# POWER_DISTRIBUTION.net
KiCad netlist of a schematic drawn in Altium Designer
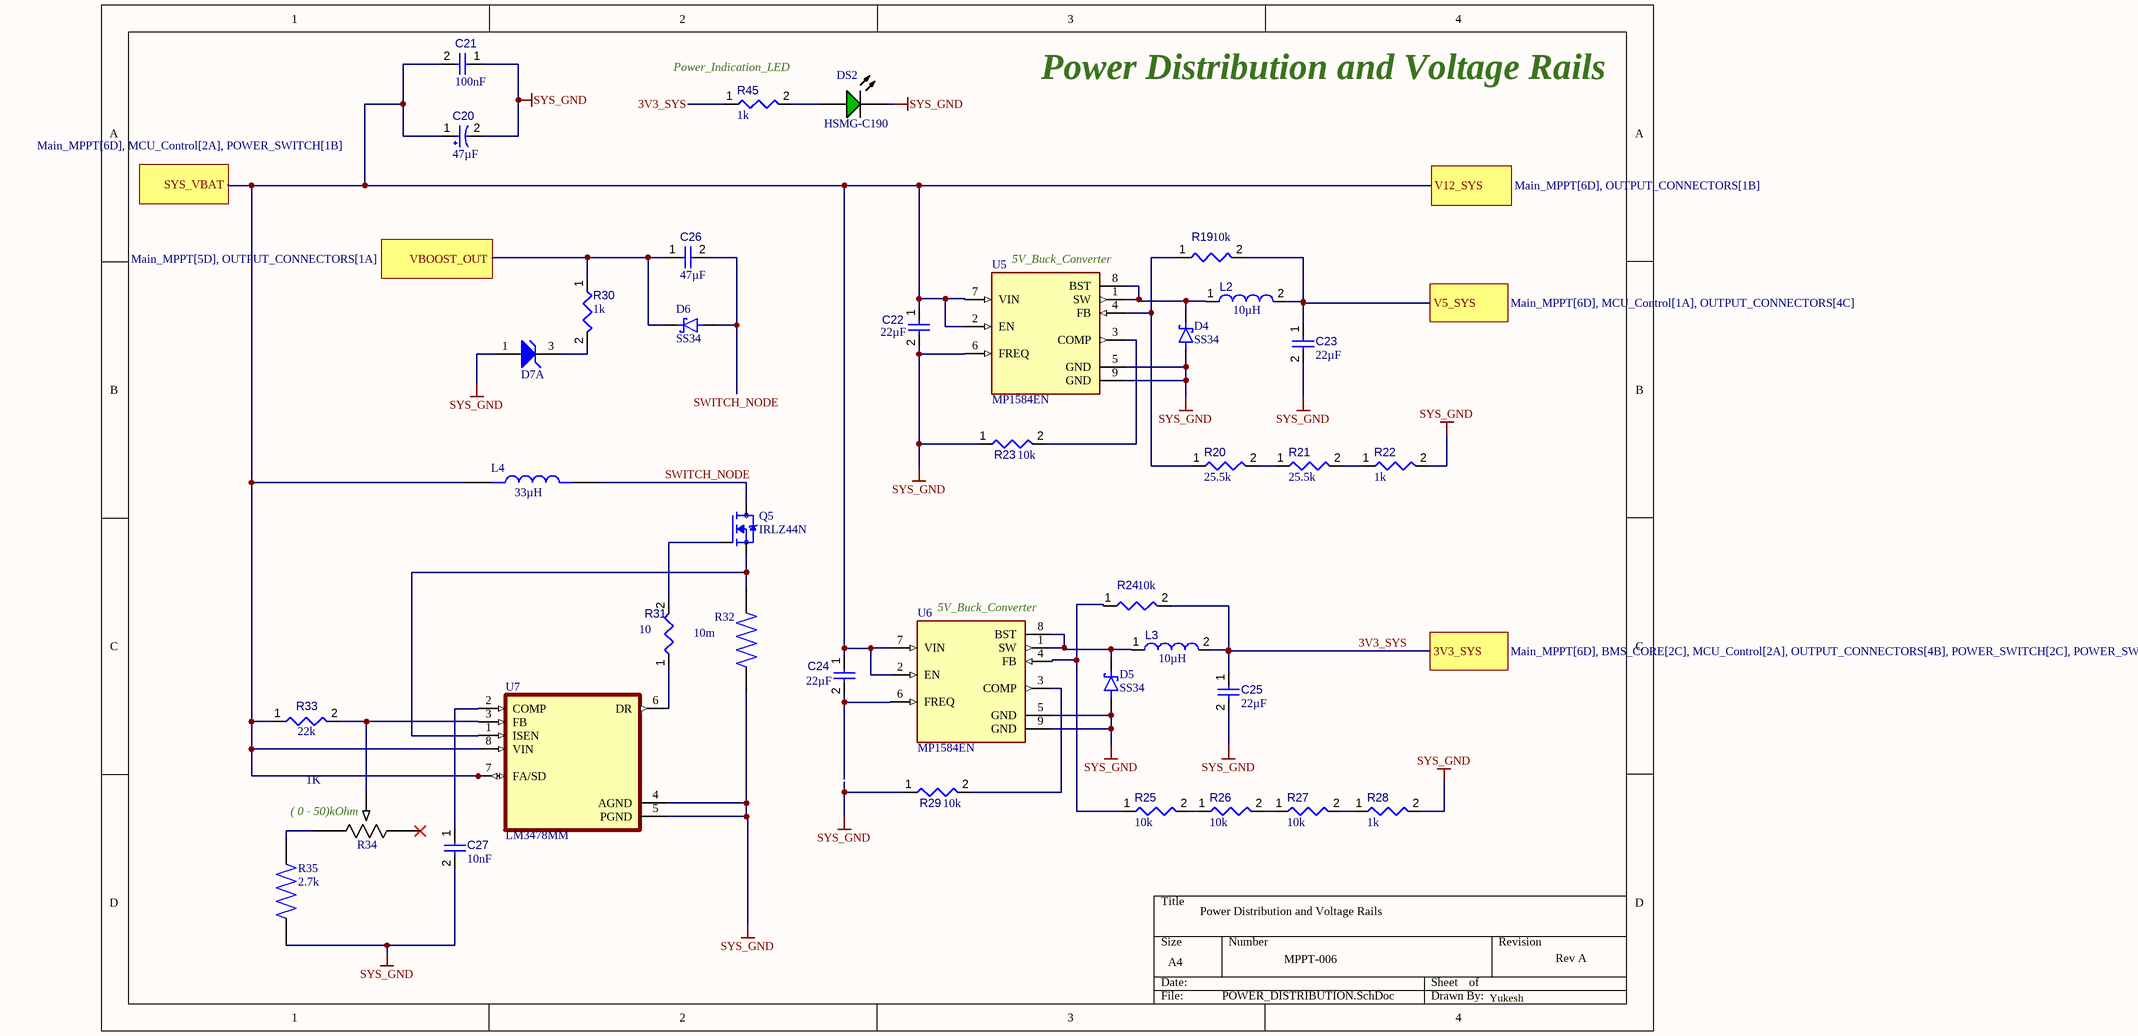
[diagram p0: POWER_DISTRIBUTION.SchDoc]

(export (version "E")
  (design (tool "Eeschema 10.0.6"))
  (components
    (comp (ref "C20")
      (value "47µF")
      (footprint "CAPPR55-250-1120X630X1220")
      (description "Aluminum Electrolytic Capacitor, 47 uF, +/- 20%, 50 V, -40 to 85 degC, 2-Pin THD, RoHS, Bulk")
      (fields (field (name "MANUFACTURER") "Panasonic") (field (name "TOLERANCE") "20%"))
      (libsource (lib "YUKESH S") (part "CAP-P-2"))
    )
    (comp (ref "C21")
      (value "100nF")
      (footprint "CAPC0402(1005)60_L")
      (description "Chip Capacitor, 100nF +/-20%, 50V, 0402, Thickness 0.6 mm")
      (fields (field (name "TOLERANCE") "10%") (field (name "Comment") "Capacitor 100nF +/-20% 50V 0402"))
      (libsource (lib "YUKESH S") (part "CAP-NP-2"))
    )
    (comp (ref "C22")
      (value "22µF")
      (footprint "CAPC0805(2012)145_L")
      (description "Chip Capacitor, 22µF +/-40%, 16V, 0805, Thickness 1.45 mm")
      (fields (field (name "TOLERANCE") "5%") (field (name "Comment") "Capacitor 22µF +/-40% 16V 0805"))
      (libsource (lib "YUKESH S") (part "CAP-NP-2"))
    )
    (comp (ref "C23")
      (value "22µF")
      (footprint "CAPC0805(2012)145_L")
      (description "Chip Capacitor, 22µF +/-40%, 16V, 0805, Thickness 1.45 mm")
      (fields (field (name "TOLERANCE") "5%") (field (name "Comment") "Capacitor 22µF +/-40% 16V 0805"))
      (libsource (lib "YUKESH S") (part "CAP-NP-2"))
    )
    (comp (ref "C24")
      (value "22µF")
      (footprint "CAPC0805(2012)145_L")
      (description "Chip Capacitor, 22µF +/-40%, 16V, 0805, Thickness 1.45 mm")
      (fields (field (name "TOLERANCE") "5%") (field (name "Comment") "Capacitor 22µF +/-40% 16V 0805"))
      (libsource (lib "YUKESH S") (part "CAP-NP-2"))
    )
    (comp (ref "C25")
      (value "22µF")
      (footprint "CAPC0805(2012)145_L")
      (description "Chip Capacitor, 22µF +/-40%, 16V, 0805, Thickness 1.45 mm")
      (fields (field (name "TOLERANCE") "5%") (field (name "Comment") "Capacitor 22µF +/-40% 16V 0805"))
      (libsource (lib "YUKESH S") (part "CAP-NP-2"))
    )
    (comp (ref "C26")
      (value "47µF")
      (footprint "CAPC0805(2012)145_L")
      (description "Chip Capacitor, 47µF +/-40%, 6.3V, 0805, Thickness 1.45 mm")
      (fields (field (name "TOLERANCE") "10%") (field (name "Comment") "Capacitor 47µF +/-40% 6.3V 0805"))
      (libsource (lib "YUKESH S") (part "CAP-NP-2"))
    )
    (comp (ref "C27")
      (value "10nF")
      (footprint "CAPC0402(1005)60_L")
      (description "Chip Capacitor, 10nF +/-20%, 50V, 0402, Thickness 0.6 mm")
      (fields (field (name "TOLERANCE") "5%") (field (name "Comment") "Capacitor 10nF +/-20% 50V 0402"))
      (libsource (lib "YUKESH S") (part "CAP-NP-2"))
    )
    (comp (ref "D4")
      (value "SS34")
      (footprint "Copy of DIOM7959X265N")
      (description "Diode Schottky 40 V 3A Surface Mount SMC (DO-214AB)")
      (fields (field (name "MF") "onsemi"))
      (libsource (lib "YUKESH S") (part "SS34"))
    )
    (comp (ref "D5")
      (value "SS34")
      (footprint "Copy of DIOM7959X265N")
      (description "Diode Schottky 40 V 3A Surface Mount SMC (DO-214AB)")
      (fields (field (name "MF") "onsemi"))
      (libsource (lib "YUKESH S") (part "SS34"))
    )
    (comp (ref "D6")
      (value "SS34")
      (footprint "Copy of DIOM7959X265N")
      (description "Diode Schottky 40 V 3A Surface Mount SMC (DO-214AB)")
      (fields (field (name "MF") "onsemi"))
      (libsource (lib "YUKESH S") (part "SS34"))
    )
    (comp (ref "D7")
      (value "BZX84C47LT1G")
      (footprint "ONSC-SOT-23-3-318-08_V")
      (description "Zener Voltage Regulator, 225 mW, 3-Pin SOT-23, Pb-Free, Tape and Reel")
      (fields (field (name "MANUFACTURER") "On Semiconductor"))
      (libsource (lib "Altium Content Vault") (part "ONSC-A1K3-3"))
    )
    (comp (ref "DS2")
      (value "HSMG-C190")
      (footprint "AVAG-HSMX-C190_V")
      (description "LED Uni-Color Green, 52 mW, 20 mA, -40 to 85 degC, 2-Pin SMD, RoHS, Tape and Reel")
      (fields (field (name "POWER") "52mW") (field (name "MANUFACTURER") "Avago"))
      (libsource (lib "YUKESH S") (part "LED-GREEN-AK-2"))
    )
    (comp (ref "L2")
      (value "10µH")
      (footprint "INDR62-500-1100X850X1100")
      (description "Radial Inductor, 10 uH, +/- 10%, 3 A, -55 to 105 degC, 2-Pin THD, RoHS, Bulk")
      (fields (field (name "TOLERANCE") "10%") (field (name "MANUFACTURER") "Bourns"))
      (libsource (lib "YUKESH S") (part "IND-2"))
    )
    (comp (ref "L3")
      (value "10µH")
      (footprint "INDR62-500-1100X850X1100")
      (description "Radial Inductor, 10 uH, +/- 10%, 3 A, -55 to 105 degC, 2-Pin THD, RoHS, Bulk")
      (fields (field (name "TOLERANCE") "10%") (field (name "MANUFACTURER") "Bourns"))
      (libsource (lib "YUKESH S") (part "IND-2"))
    )
    (comp (ref "L4")
      (value "33µH")
      (footprint "IND_ETQP4M330YFN")
      (description "FIXED IND 33UH 2.5A 189.2MOHM SM")
      (fields (field (name "MF") "Panasonic") (field (name "MP") "ETQP4M330YFN"))
      (libsource (lib "YUKESH S") (part "ETQP4M330YFN"))
    )
    (comp (ref "Q5")
      (value "IRLZ44N")
      (footprint "TO254P1054X469X1930-3")
      (description "N-Channel 55 V 47A (Tc) 3.8W (Ta), 110W (Tc) Surface Mount D2PAK")
      (fields (field (name "MF") "Infineon / IR"))
      (libsource (lib "YUKESH S") (part "IRLZ44N"))
    )
    (comp (ref "R19")
      (value "10k")
      (footprint "RESC0402(1005)_L")
      (description "Chip Resistor, 10 kOhms, +/-1 %, 63 mW, -55 to 125 degC, 0402")
      (fields (field (name "POWER") "63mW") (field (name "TOLERANCE") "1%"))
      (libsource (lib "YUKESH S") (part "RES-2"))
    )
    (comp (ref "R20")
      (value "25.5k")
      (footprint "RESC0402(1005)_L")
      (description "25K5 0.063W 1% 0402 (1005 Metric)  SMD")
      (fields (field (name "TOLERANCE") "1%") (field (name "POWER") "63mW"))
      (libsource (lib "YUKESH S") (part "25D5KR2F"))
    )
    (comp (ref "R21")
      (value "25.5k")
      (footprint "RESC0402(1005)_L")
      (description "25K5 0.063W 1% 0402 (1005 Metric)  SMD")
      (fields (field (name "TOLERANCE") "1%") (field (name "POWER") "63mW"))
      (libsource (lib "YUKESH S") (part "25D5KR2F"))
    )
    (comp (ref "R22")
      (value "1k")
      (footprint "RESC0402(1005)_L")
      (description "1K 0.063W 5% 0402 (1005 Metric)  SMD")
      (fields (field (name "POWER") "63mW") (field (name "TOLERANCE") "5%"))
      (libsource (lib "YUKESH S") (part "1KR2J"))
    )
    (comp (ref "R23")
      (value "10k")
      (footprint "RESC0402(1005)_L")
      (description "Chip Resistor, 10 kOhms, +/-1 %, 63 mW, -55 to 125 degC, 0402")
      (fields (field (name "POWER") "63mW") (field (name "TOLERANCE") "1%"))
      (libsource (lib "YUKESH S") (part "RES-2"))
    )
    (comp (ref "R24")
      (value "10k")
      (footprint "RESC0402(1005)_L")
      (description "Chip Resistor, 10 kOhms, +/-1 %, 63 mW, -55 to 125 degC, 0402")
      (fields (field (name "POWER") "63mW") (field (name "TOLERANCE") "1%"))
      (libsource (lib "YUKESH S") (part "RES-2"))
    )
    (comp (ref "R25")
      (value "10k")
      (footprint "RESC0402(1005)_L")
      (description "10K 0.063W 1% 0402 (1005 Metric)  SMD")
      (fields (field (name "POWER") "63mW") (field (name "TOLERANCE") "1%"))
      (libsource (lib "YUKESH S") (part "10KR2F"))
    )
    (comp (ref "R26")
      (value "10k")
      (footprint "RESC0402(1005)_L")
      (description "10K 0.063W 1% 0402 (1005 Metric)  SMD")
      (fields (field (name "POWER") "63mW") (field (name "TOLERANCE") "1%"))
      (libsource (lib "YUKESH S") (part "10KR2F"))
    )
    (comp (ref "R27")
      (value "10k")
      (footprint "RESC0402(1005)_L")
      (description "10K 0.063W 1% 0402 (1005 Metric)  SMD")
      (fields (field (name "POWER") "63mW") (field (name "TOLERANCE") "1%"))
      (libsource (lib "YUKESH S") (part "10KR2F"))
    )
    (comp (ref "R28")
      (value "1k")
      (footprint "RESC0402(1005)_L")
      (description "1K 0.063W 5% 0402 (1005 Metric)  SMD")
      (fields (field (name "POWER") "63mW") (field (name "TOLERANCE") "5%"))
      (libsource (lib "YUKESH S") (part "1KR2J"))
    )
    (comp (ref "R29")
      (value "10k")
      (footprint "RESC0402(1005)_L")
      (description "Chip Resistor, 10 kOhms, +/-1 %, 63 mW, -55 to 125 degC, 0402")
      (fields (field (name "POWER") "63mW") (field (name "TOLERANCE") "1%"))
      (libsource (lib "YUKESH S") (part "RES-2"))
    )
    (comp (ref "R30")
      (value "1k")
      (footprint "RESC0805(2012)_L")
      (description "1K 0.125W 5% 0805 (2012 Metric)  SMD")
      (fields (field (name "TOLERANCE") "5%") (field (name "POWER") "125mW"))
      (libsource (lib "YUKESH S") (part "1KR5J"))
    )
    (comp (ref "R31")
      (value "10")
      (footprint "RESC0402(1005)_L")
      (description "10R 0.063W 1% 0402 (1005 Metric)  SMD")
      (fields (field (name "TOLERANCE") "1%") (field (name "POWER") "63mW"))
      (libsource (lib "YUKESH S") (part "10R2F"))
    )
    (comp (ref "R32")
      (value "10m")
      (footprint "RESC6331X88N")
      (fields (field (name "MP") "WSL2512R0100FEA18") (field (name "MF") "Vishay Intertechnology"))
      (libsource (lib "YUKESH S") (part "WSL2512R0100FEA18"))
    )
    (comp (ref "R33")
      (value "22k")
      (footprint "RESC0402(1005)_L")
      (description "22K 0.063W 1% 0402 (1005 Metric)  SMD")
      (fields (field (name "TOLERANCE") "1%") (field (name "POWER") "63mW"))
      (libsource (lib "YUKESH S") (part "22KR2F"))
    )
    (comp (ref "R34")
      (value "1K")
      (footprint "POT3_T63XB")
      (description "T63 XB 50K 10% TU e3")
      (fields
        (field (name "MANUFACTURER_PART_NUMBER") "T63XB503KT20")
        (field (name "COPYRIGHT") "Copyright (C) 2026 Ultra Librarian. All rights reserved.")
      )
      (libsource (lib "YUKESH S") (part "T63XB503KT20"))
    )
    (comp (ref "R35")
      (value "2.7k")
      (footprint "RES_ERJ2RHD2702X")
      (description "ERJ2R Resistor 0.063W 27K 0.5% 50ppm")
      (fields (field (name "MF") "Panasonic") (field (name "MP") "ERJ2RHD2702X"))
      (libsource (lib "YUKESH S") (part "ERJ2RHD2702X"))
    )
    (comp (ref "R45")
      (value "1k")
      (footprint "RESC0402(1005)_L")
      (description "1K 0.063W 5% 0402 (1005 Metric)  SMD")
      (fields (field (name "POWER") "63mW") (field (name "TOLERANCE") "5%"))
      (libsource (lib "YUKESH S") (part "1KR2J"))
    )
    (comp (ref "U5")
      (value "MP1584EN")
      (footprint "SOIC127P600X170-9N")
      (fields (field (name "MF") "Monolithic Power"))
      (libsource (lib "YUKESH S") (part "MP1584EN"))
    )
    (comp (ref "U6")
      (value "MP1584EN")
      (footprint "SOIC127P600X170-9N")
      (fields (field (name "MF") "Monolithic Power"))
      (libsource (lib "YUKESH S") (part "MP1584EN"))
    )
    (comp (ref "U7")
      (value "LM3478MM")
      (footprint "SOP65P490X110-8N")
      (description "2.97~40V Wide Input Range Boost/SEPIC/Flyback DC-DC Controller")
      (fields (field (name "MP") "LM3478MM/NOPB") (field (name "MF") "Texas Instruments"))
      (libsource (lib "YUKESH S") (part "LM3478MM"))
    )
  )
  (nets
    (net (code "1") (name "/3V3_SYS") (class "Default")
      (node (ref "C25") (pin "1") (pinfunction "1_1") (pintype "passive"))
      (node (ref "L3") (pin "2") (pinfunction "2_2") (pintype "passive"))
      (node (ref "R24") (pin "2") (pinfunction "2_2") (pintype "passive"))
      (node (ref "R45") (pin "1") (pinfunction "1_1") (pintype "passive"))
    )
    (net (code "2") (name "/SWITCH_NODE") (class "Default")
      (node (ref "C26") (pin "2") (pinfunction "2_2") (pintype "passive"))
      (node (ref "D6") (pin "A") (pinfunction "A_A") (pintype "passive"))
      (node (ref "L4") (pin "2") (pinfunction "2_2") (pintype "passive"))
      (node (ref "Q5") (pin "2") (pinfunction "D_2") (pintype "passive"))
    )
    (net (code "3") (name "/SYS_VBAT") (class "Default")
      (node (ref "C20") (pin "1") (pinfunction "1_1") (pintype "passive"))
      (node (ref "C21") (pin "2") (pinfunction "2_2") (pintype "passive"))
      (node (ref "C22") (pin "1") (pinfunction "1_1") (pintype "passive"))
      (node (ref "C24") (pin "1") (pinfunction "1_1") (pintype "passive"))
      (node (ref "L4") (pin "1") (pinfunction "1_1") (pintype "passive"))
      (node (ref "R33") (pin "1") (pinfunction "1_1") (pintype "passive"))
      (node (ref "U5") (pin "2") (pinfunction "EN_2") (pintype "input"))
      (node (ref "U5") (pin "7") (pinfunction "VIN_7") (pintype "input"))
      (node (ref "U6") (pin "2") (pinfunction "EN_2") (pintype "input"))
      (node (ref "U6") (pin "7") (pinfunction "VIN_7") (pintype "input"))
      (node (ref "U7") (pin "7") (pinfunction "FA/SD_7") (pintype "bidirectional"))
      (node (ref "U7") (pin "8") (pinfunction "VIN_8") (pintype "input"))
    )
    (net (code "4") (name "/V5_SYS") (class "Default")
      (node (ref "C23") (pin "1") (pinfunction "1_1") (pintype "passive"))
      (node (ref "L2") (pin "2") (pinfunction "2_2") (pintype "passive"))
      (node (ref "R19") (pin "2") (pinfunction "2_2") (pintype "passive"))
    )
    (net (code "5") (name "/VBOOST_OUT") (class "Default")
      (node (ref "C26") (pin "1") (pinfunction "1_1") (pintype "passive"))
      (node (ref "D6") (pin "C") (pinfunction "K_C") (pintype "passive"))
      (node (ref "R30") (pin "1") (pinfunction "1_1") (pintype "passive"))
    )
    (net (code "6") (name "Net-(D4-K)") (class "Default")
      (node (ref "D4") (pin "C") (pinfunction "K_C") (pintype "passive"))
      (node (ref "L2") (pin "1") (pinfunction "1_1") (pintype "passive"))
      (node (ref "U5") (pin "1") (pinfunction "SW_1") (pintype "output"))
      (node (ref "U5") (pin "8") (pinfunction "BST_8") (pintype "passive"))
    )
    (net (code "7") (name "Net-(D5-K)") (class "Default")
      (node (ref "D5") (pin "C") (pinfunction "K_C") (pintype "passive"))
      (node (ref "L3") (pin "1") (pinfunction "1_1") (pintype "passive"))
      (node (ref "U6") (pin "1") (pinfunction "SW_1") (pintype "output"))
      (node (ref "U6") (pin "8") (pinfunction "BST_8") (pintype "passive"))
    )
    (net (code "8") (name "Net-(D7A-K)") (class "Default")
      (node (ref "D7") (pin "3") (pinfunction "K_3") (pintype "passive"))
      (node (ref "R30") (pin "2") (pinfunction "2_2") (pintype "passive"))
    )
    (net (code "9") (name "Net-(DS2-A)") (class "Default")
      (node (ref "DS2") (pin "1") (pinfunction "A_1") (pintype "passive"))
      (node (ref "R45") (pin "2") (pinfunction "2_2") (pintype "passive"))
    )
    (net (code "10") (name "Net-(Q5-G)") (class "Default")
      (node (ref "Q5") (pin "1") (pinfunction "G_1") (pintype "passive"))
      (node (ref "R31") (pin "2") (pinfunction "2_2") (pintype "passive"))
    )
    (net (code "11") (name "Net-(Q5-S)") (class "Default")
      (node (ref "Q5") (pin "3") (pinfunction "S_3") (pintype "passive"))
      (node (ref "R32") (pin "2") (pinfunction "2_2") (pintype "passive"))
      (node (ref "U7") (pin "1") (pinfunction "ISEN_1") (pintype "input"))
    )
    (net (code "12") (name "Net-(R20-Pad2)") (class "Default")
      (node (ref "R20") (pin "2") (pinfunction "2_2") (pintype "passive"))
      (node (ref "R21") (pin "1") (pinfunction "1_1") (pintype "passive"))
    )
    (net (code "13") (name "Net-(R21-Pad2)") (class "Default")
      (node (ref "R21") (pin "2") (pinfunction "2_2") (pintype "passive"))
      (node (ref "R22") (pin "1") (pinfunction "1_1") (pintype "passive"))
    )
    (net (code "14") (name "Net-(R25-Pad2)") (class "Default")
      (node (ref "R25") (pin "2") (pinfunction "2_2") (pintype "passive"))
      (node (ref "R26") (pin "1") (pinfunction "1_1") (pintype "passive"))
    )
    (net (code "15") (name "Net-(R26-Pad2)") (class "Default")
      (node (ref "R26") (pin "2") (pinfunction "2_2") (pintype "passive"))
      (node (ref "R27") (pin "1") (pinfunction "1_1") (pintype "passive"))
    )
    (net (code "16") (name "Net-(R27-Pad2)") (class "Default")
      (node (ref "R27") (pin "2") (pinfunction "2_2") (pintype "passive"))
      (node (ref "R28") (pin "1") (pinfunction "1_1") (pintype "passive"))
    )
    (net (code "17") (name "Net-(R34-Pad1)") (class "Default")
      (node (ref "R34") (pin "1") (pinfunction "1_1") (pintype "passive"))
      (node (ref "R35") (pin "1") (pinfunction "1_1") (pintype "passive"))
    )
    (net (code "18") (name "Net-(U5-COMP)") (class "Default")
      (node (ref "R23") (pin "2") (pinfunction "2_2") (pintype "passive"))
      (node (ref "U5") (pin "3") (pinfunction "COMP_3") (pintype "output"))
    )
    (net (code "19") (name "Net-(U5-FB)") (class "Default")
      (node (ref "R19") (pin "1") (pinfunction "1_1") (pintype "passive"))
      (node (ref "R20") (pin "1") (pinfunction "1_1") (pintype "passive"))
      (node (ref "U5") (pin "4") (pinfunction "FB_4") (pintype "input"))
    )
    (net (code "20") (name "Net-(U6-COMP)") (class "Default")
      (node (ref "R29") (pin "2") (pinfunction "2_2") (pintype "passive"))
      (node (ref "U6") (pin "3") (pinfunction "COMP_3") (pintype "output"))
    )
    (net (code "21") (name "Net-(U6-FB)") (class "Default")
      (node (ref "R24") (pin "1") (pinfunction "1_1") (pintype "passive"))
      (node (ref "R25") (pin "1") (pinfunction "1_1") (pintype "passive"))
      (node (ref "U6") (pin "4") (pinfunction "FB_4") (pintype "input"))
    )
    (net (code "22") (name "Net-(U6-FREQ)") (class "Default")
      (node (ref "C24") (pin "2") (pinfunction "2_2") (pintype "passive"))
      (node (ref "U6") (pin "6") (pinfunction "FREQ_6") (pintype "input"))
    )
    (net (code "23") (name "Net-(U7-COMP)") (class "Default")
      (node (ref "C27") (pin "1") (pinfunction "1_1") (pintype "passive"))
      (node (ref "U7") (pin "2") (pinfunction "COMP_2") (pintype "input"))
    )
    (net (code "24") (name "Net-(U7-DR)") (class "Default")
      (node (ref "R31") (pin "1") (pinfunction "1_1") (pintype "passive"))
      (node (ref "U7") (pin "6") (pinfunction "DR_6") (pintype "output"))
    )
    (net (code "25") (name "Net-(U7-FB)") (class "Default")
      (node (ref "R33") (pin "2") (pinfunction "2_2") (pintype "passive"))
      (node (ref "R34") (pin "2") (pinfunction "2_2") (pintype "passive"))
      (node (ref "U7") (pin "3") (pinfunction "FB_3") (pintype "input"))
    )
    (net (code "26") (name "SYS_GND") (class "Default")
      (node (ref "C20") (pin "2") (pinfunction "2_2") (pintype "passive"))
      (node (ref "C21") (pin "1") (pinfunction "1_1") (pintype "passive"))
      (node (ref "C22") (pin "2") (pinfunction "2_2") (pintype "passive"))
      (node (ref "C23") (pin "2") (pinfunction "2_2") (pintype "passive"))
      (node (ref "C25") (pin "2") (pinfunction "2_2") (pintype "passive"))
      (node (ref "C27") (pin "2") (pinfunction "2_2") (pintype "passive"))
      (node (ref "D4") (pin "A") (pinfunction "A_A") (pintype "passive"))
      (node (ref "D5") (pin "A") (pinfunction "A_A") (pintype "passive"))
      (node (ref "D7") (pin "1") (pinfunction "A_1") (pintype "passive"))
      (node (ref "DS2") (pin "2") (pinfunction "K_2") (pintype "passive"))
      (node (ref "R22") (pin "2") (pinfunction "2_2") (pintype "passive"))
      (node (ref "R23") (pin "1") (pinfunction "1_1") (pintype "passive"))
      (node (ref "R28") (pin "2") (pinfunction "2_2") (pintype "passive"))
      (node (ref "R29") (pin "1") (pinfunction "1_1") (pintype "passive"))
      (node (ref "R32") (pin "1") (pinfunction "1_1") (pintype "passive"))
      (node (ref "R35") (pin "2") (pinfunction "2_2") (pintype "passive"))
      (node (ref "U5") (pin "5") (pinfunction "GND_5") (pintype "power_in"))
      (node (ref "U5") (pin "6") (pinfunction "FREQ_6") (pintype "input"))
      (node (ref "U5") (pin "9") (pinfunction "GND_9") (pintype "power_in"))
      (node (ref "U6") (pin "5") (pinfunction "GND_5") (pintype "power_in"))
      (node (ref "U6") (pin "9") (pinfunction "GND_9") (pintype "power_in"))
      (node (ref "U7") (pin "4") (pinfunction "AGND_4") (pintype "power_in"))
      (node (ref "U7") (pin "5") (pinfunction "PGND_5") (pintype "power_in"))
    )
    (net (code "27") (name "unconnected-(R34-Pad3)") (class "Default")
      (node (ref "R34") (pin "3") (pinfunction "3_3") (pintype "passive+no_connect"))
    )
  )
)
